# Module.net
KiCad netlist of a schematic drawn in Altium Designer
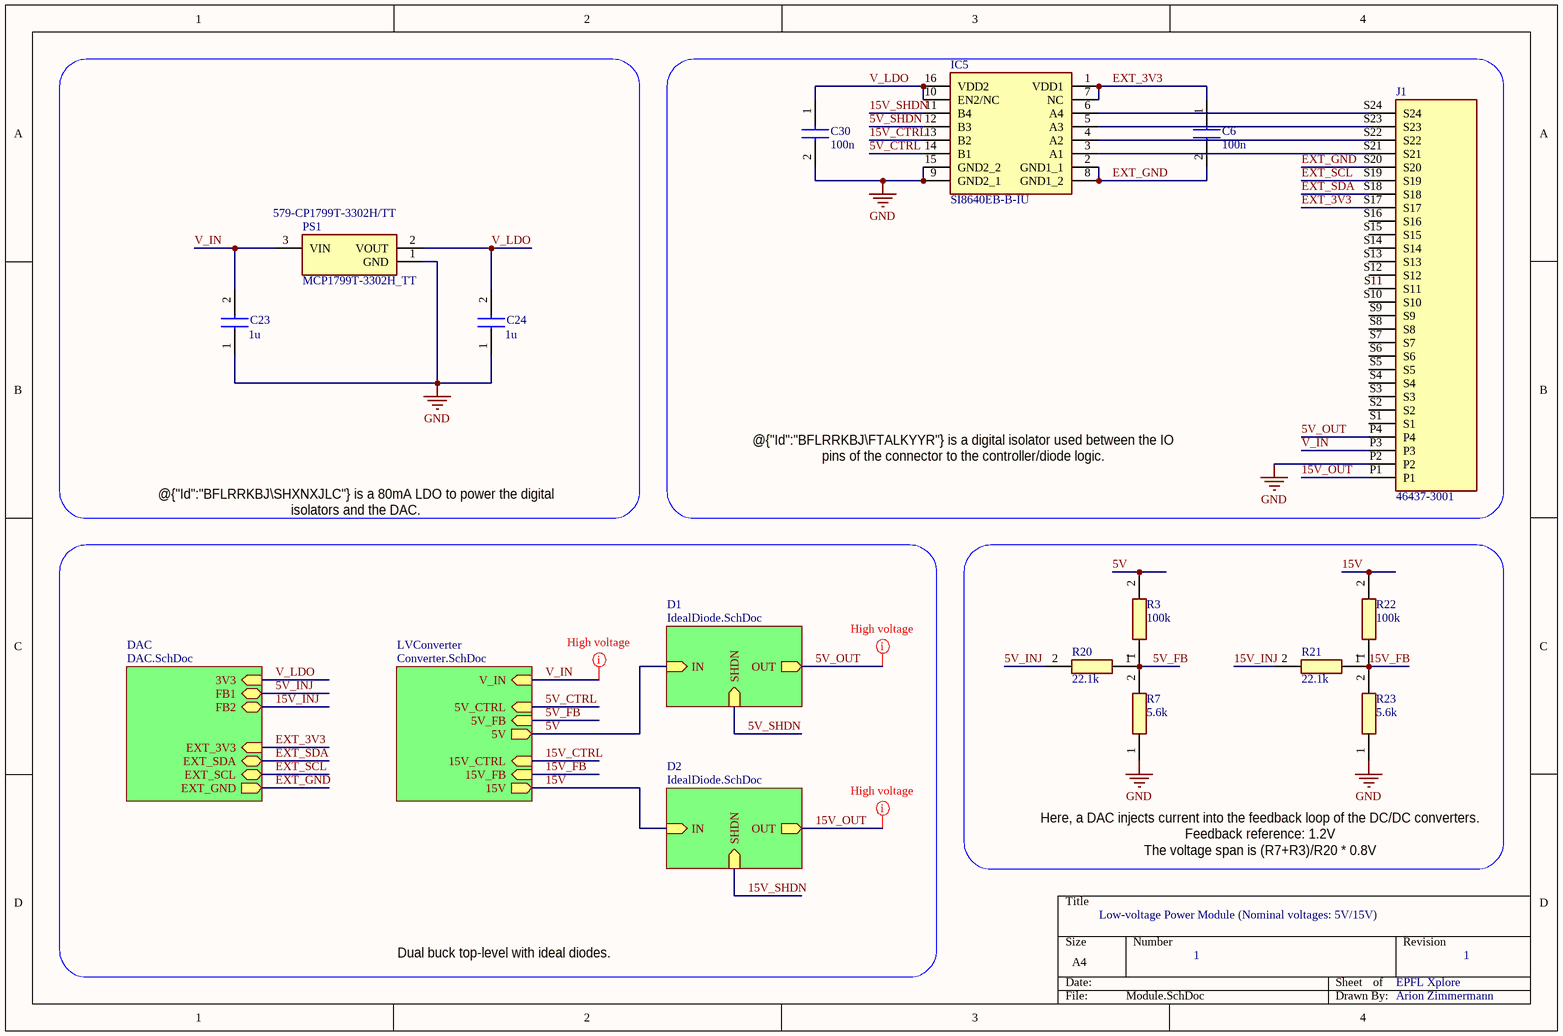
[diagram p0: Module.SchDoc]

(export (version "E")
  (design (tool "Eeschema 10.0.6"))
  (components
    (comp (ref "C6")
      (value "100n")
      (footprint "SamacSys:CAPC1608X95N")
      (description "Capacitor")
      (fields
        (field (name "MANUFACTURER_PART_NUMBER") "C0603C104K5RACTU")
        (field (name "MOUSER PART NUMBER") "80-C0603C104K5R")
      )
      (libsource (lib "*") (part "C0603C104K5RACTU"))
    )
    (comp (ref "C23")
      (value "1u")
      (footprint "SamacSys:CAPC3216X110N")
      (description "Capacitor")
      (fields
        (field (name "MANUFACTURER_PART_NUMBER") "C1206C105K5RAC")
        (field (name "MOUSER PART NUMBER") "80-C1206C105K5RAC")
      )
      (libsource (lib "*") (part "C1206C105K5RAC"))
    )
    (comp (ref "C24")
      (value "1u")
      (footprint "SamacSys:CAPC3216X110N")
      (description "Capacitor")
      (fields
        (field (name "MANUFACTURER_PART_NUMBER") "C1206C105K5RAC")
        (field (name "MOUSER PART NUMBER") "80-C1206C105K5RAC")
      )
      (libsource (lib "*") (part "C1206C105K5RAC"))
    )
    (comp (ref "C30")
      (value "100n")
      (footprint "SamacSys:CAPC1608X95N")
      (description "Capacitor")
      (fields
        (field (name "MANUFACTURER_PART_NUMBER") "C0603C104K5RACTU")
        (field (name "MOUSER PART NUMBER") "80-C0603C104K5R")
      )
      (libsource (lib "*") (part "C0603C104K5RACTU"))
    )
    (comp (ref "IC5")
      (value "SI8640EB-B-IU")
      (footprint "SamacSys:SOP64P600X175-16N")
      (description "Integrated Circuit")
      (fields (field (name "MOUSER PART NUMBER") "634-SI8640EB-B-IU"))
      (libsource (lib "*") (part "SI8640EB-B-IU"))
    )
    (comp (ref "J1")
      (value "46437-3001")
      (footprint "464373001")
      (description "Connector")
      (fields (field (name "MOUSER PART NUMBER") "538-46437-3001"))
      (libsource (lib "SamacSys") (part "46437-3001"))
    )
    (comp (ref "PS1")
      (value "MCP1799T-3302H_TT")
      (footprint "SamacSys:SOT95P237X112-3N")
      (description "Power Supply")
      (fields
        (field (name "MANUFACTURER_PART_NUMBER") "MCP1799T-3302H/TT")
        (field (name "MOUSER PART NUMBER") "579-CP1799T-3302H/TT")
        (field (name "SUPPLIER PART NUMBER 1") "579-CP1799T-3302H/TT")
      )
      (libsource (lib "*") (part "MCP1799T-3302H_TT"))
    )
    (comp (ref "R3")
      (value "100k")
      (footprint "SamacSys:RESC1608X55N")
      (description "Resistor")
      (fields
        (field (name "MANUFACTURER_PART_NUMBER") "CRCW0603100KFKEAC")
        (field (name "MOUSER PART NUMBER") "71-CRCW0603100KFKEAC")
      )
      (libsource (lib "*") (part "CRCW0603100KFKEAC"))
    )
    (comp (ref "R7")
      (value "5.6k")
      (footprint "SamacSys:RESC1608X50N")
      (description "Resistor")
      (fields
        (field (name "MANUFACTURER_PART_NUMBER") "CRCW06035K62FKEB")
        (field (name "MOUSER PART NUMBER") "71-CRCW06035K62FKEB")
      )
      (libsource (lib "*") (part "CRCW06035K62FKEB"))
    )
    (comp (ref "R20")
      (value "22.1k")
      (footprint "SamacSys:RESC1608X50N")
      (description "Resistor")
      (fields
        (field (name "MANUFACTURER_PART_NUMBER") "CRCW06037K50FKEB")
        (field (name "MOUSER PART NUMBER") "71-CRCW06037K50FKEB")
      )
      (libsource (lib "*") (part "CRCW06037K50FKEB"))
    )
    (comp (ref "R21")
      (value "22.1k")
      (footprint "SamacSys:RESC1608X50N")
      (description "Resistor")
      (fields
        (field (name "MANUFACTURER_PART_NUMBER") "CRCW06037K50FKEB")
        (field (name "MOUSER PART NUMBER") "71-CRCW06037K50FKEB")
      )
      (libsource (lib "*") (part "CRCW06037K50FKEB"))
    )
    (comp (ref "R22")
      (value "100k")
      (footprint "SamacSys:RESC1608X55N")
      (description "Resistor")
      (fields
        (field (name "MANUFACTURER_PART_NUMBER") "CRCW0603100KFKEAC")
        (field (name "MOUSER PART NUMBER") "71-CRCW0603100KFKEAC")
      )
      (libsource (lib "*") (part "CRCW0603100KFKEAC"))
    )
    (comp (ref "R23")
      (value "5.6k")
      (footprint "SamacSys:RESC1608X50N")
      (description "Resistor")
      (fields
        (field (name "MANUFACTURER_PART_NUMBER") "CRCW06035K62FKEB")
        (field (name "MOUSER PART NUMBER") "71-CRCW06035K62FKEB")
      )
      (libsource (lib "*") (part "CRCW06035K62FKEB"))
    )
  )
  (nets
    (net (code "1") (name "/5V") (class "Default")
      (node (ref "R3") (pin "2") (pinfunction "2_2") (pintype "passive"))
    )
    (net (code "2") (name "/5V_CTRL") (class "Default")
      (node (ref "IC5") (pin "14") (pinfunction "B1_14") (pintype "passive"))
    )
    (net (code "3") (name "/5V_FB") (class "Default")
      (node (ref "R20") (pin "1") (pinfunction "1_1") (pintype "passive"))
      (node (ref "R3") (pin "1") (pinfunction "1_1") (pintype "passive"))
      (node (ref "R7") (pin "2") (pinfunction "2_2") (pintype "passive"))
    )
    (net (code "4") (name "/5V_INJ") (class "Default")
      (node (ref "R20") (pin "2") (pinfunction "2_2") (pintype "passive"))
    )
    (net (code "5") (name "/5V_OUT") (class "Default")
      (node (ref "J1") (pin "P4") (pinfunction "P4_P4") (pintype "passive"))
    )
    (net (code "6") (name "/5V_SHDN") (class "Default")
      (node (ref "IC5") (pin "12") (pinfunction "B3_12") (pintype "passive"))
    )
    (net (code "7") (name "/15V") (class "Default")
      (node (ref "R22") (pin "2") (pinfunction "2_2") (pintype "passive"))
    )
    (net (code "8") (name "/15V_CTRL") (class "Default")
      (node (ref "IC5") (pin "13") (pinfunction "B2_13") (pintype "passive"))
    )
    (net (code "9") (name "/15V_FB") (class "Default")
      (node (ref "R21") (pin "1") (pinfunction "1_1") (pintype "passive"))
      (node (ref "R22") (pin "1") (pinfunction "1_1") (pintype "passive"))
      (node (ref "R23") (pin "2") (pinfunction "2_2") (pintype "passive"))
    )
    (net (code "10") (name "/15V_INJ") (class "Default")
      (node (ref "R21") (pin "2") (pinfunction "2_2") (pintype "passive"))
    )
    (net (code "11") (name "/15V_OUT") (class "Default")
      (node (ref "J1") (pin "P1") (pinfunction "P1_P1") (pintype "passive"))
    )
    (net (code "12") (name "/15V_SHDN") (class "Default")
      (node (ref "IC5") (pin "11") (pinfunction "B4_11") (pintype "passive"))
    )
    (net (code "13") (name "/EXT_3V3") (class "Default")
      (node (ref "C6") (pin "1") (pinfunction "1_1") (pintype "passive"))
      (node (ref "IC5") (pin "1") (pinfunction "VDD1_1") (pintype "passive"))
      (node (ref "IC5") (pin "7") (pinfunction "NC_7") (pintype "passive"))
      (node (ref "J1") (pin "S17") (pinfunction "S17_S17") (pintype "passive"))
    )
    (net (code "14") (name "/EXT_GND") (class "Default")
      (node (ref "C6") (pin "2") (pinfunction "2_2") (pintype "passive"))
      (node (ref "IC5") (pin "2") (pinfunction "GND1_1_2") (pintype "passive"))
      (node (ref "IC5") (pin "8") (pinfunction "GND1_2_8") (pintype "passive"))
      (node (ref "J1") (pin "S20") (pinfunction "S20_S20") (pintype "passive"))
    )
    (net (code "15") (name "/EXT_SCL") (class "Default")
      (node (ref "J1") (pin "S19") (pinfunction "S19_S19") (pintype "passive"))
    )
    (net (code "16") (name "/EXT_SDA") (class "Default")
      (node (ref "J1") (pin "S18") (pinfunction "S18_S18") (pintype "passive"))
    )
    (net (code "17") (name "/V_IN") (class "Default")
      (node (ref "C23") (pin "2") (pinfunction "2_2") (pintype "passive"))
      (node (ref "J1") (pin "P3") (pinfunction "P3_P3") (pintype "passive"))
      (node (ref "PS1") (pin "3") (pinfunction "VIN_3") (pintype "passive"))
    )
    (net (code "18") (name "/V_LDO") (class "Default")
      (node (ref "C24") (pin "2") (pinfunction "2_2") (pintype "passive"))
      (node (ref "C30") (pin "1") (pinfunction "1_1") (pintype "passive"))
      (node (ref "IC5") (pin "10") (pinfunction "EN2/NC_10") (pintype "passive"))
      (node (ref "IC5") (pin "16") (pinfunction "VDD2_16") (pintype "passive"))
      (node (ref "PS1") (pin "2") (pinfunction "VOUT_2") (pintype "passive"))
    )
    (net (code "19") (name "GND") (class "Default")
      (node (ref "C23") (pin "1") (pinfunction "1_1") (pintype "passive"))
      (node (ref "C24") (pin "1") (pinfunction "1_1") (pintype "passive"))
      (node (ref "C30") (pin "2") (pinfunction "2_2") (pintype "passive"))
      (node (ref "IC5") (pin "15") (pinfunction "GND2_2_15") (pintype "passive"))
      (node (ref "IC5") (pin "9") (pinfunction "GND2_1_9") (pintype "passive"))
      (node (ref "J1") (pin "P2") (pinfunction "P2_P2") (pintype "passive"))
      (node (ref "PS1") (pin "1") (pinfunction "GND_1") (pintype "passive"))
      (node (ref "R23") (pin "1") (pinfunction "1_1") (pintype "passive"))
      (node (ref "R7") (pin "1") (pinfunction "1_1") (pintype "passive"))
    )
    (net (code "20") (name "Net-(IC5-A1)") (class "Default")
      (node (ref "IC5") (pin "3") (pinfunction "A1_3") (pintype "passive"))
      (node (ref "J1") (pin "S21") (pinfunction "S21_S21") (pintype "passive"))
    )
    (net (code "21") (name "Net-(IC5-A2)") (class "Default")
      (node (ref "IC5") (pin "4") (pinfunction "A2_4") (pintype "passive"))
      (node (ref "J1") (pin "S22") (pinfunction "S22_S22") (pintype "passive"))
    )
    (net (code "22") (name "Net-(IC5-A3)") (class "Default")
      (node (ref "IC5") (pin "5") (pinfunction "A3_5") (pintype "passive"))
      (node (ref "J1") (pin "S23") (pinfunction "S23_S23") (pintype "passive"))
    )
    (net (code "23") (name "Net-(IC5-A4)") (class "Default")
      (node (ref "IC5") (pin "6") (pinfunction "A4_6") (pintype "passive"))
      (node (ref "J1") (pin "S24") (pinfunction "S24_S24") (pintype "passive"))
    )
    (net (code "24") (name "unconnected-(J1-PadS1)") (class "Default")
      (node (ref "J1") (pin "S1") (pinfunction "S1_S1") (pintype "passive"))
    )
    (net (code "25") (name "unconnected-(J1-PadS2)") (class "Default")
      (node (ref "J1") (pin "S2") (pinfunction "S2_S2") (pintype "passive"))
    )
    (net (code "26") (name "unconnected-(J1-PadS3)") (class "Default")
      (node (ref "J1") (pin "S3") (pinfunction "S3_S3") (pintype "passive"))
    )
    (net (code "27") (name "unconnected-(J1-PadS4)") (class "Default")
      (node (ref "J1") (pin "S4") (pinfunction "S4_S4") (pintype "passive"))
    )
    (net (code "28") (name "unconnected-(J1-PadS5)") (class "Default")
      (node (ref "J1") (pin "S5") (pinfunction "S5_S5") (pintype "passive"))
    )
    (net (code "29") (name "unconnected-(J1-PadS6)") (class "Default")
      (node (ref "J1") (pin "S6") (pinfunction "S6_S6") (pintype "passive"))
    )
    (net (code "30") (name "unconnected-(J1-PadS7)") (class "Default")
      (node (ref "J1") (pin "S7") (pinfunction "S7_S7") (pintype "passive"))
    )
    (net (code "31") (name "unconnected-(J1-PadS8)") (class "Default")
      (node (ref "J1") (pin "S8") (pinfunction "S8_S8") (pintype "passive"))
    )
    (net (code "32") (name "unconnected-(J1-PadS9)") (class "Default")
      (node (ref "J1") (pin "S9") (pinfunction "S9_S9") (pintype "passive"))
    )
    (net (code "33") (name "unconnected-(J1-PadS10)") (class "Default")
      (node (ref "J1") (pin "S10") (pinfunction "S10_S10") (pintype "passive"))
    )
    (net (code "34") (name "unconnected-(J1-PadS11)") (class "Default")
      (node (ref "J1") (pin "S11") (pinfunction "S11_S11") (pintype "passive"))
    )
    (net (code "35") (name "unconnected-(J1-PadS12)") (class "Default")
      (node (ref "J1") (pin "S12") (pinfunction "S12_S12") (pintype "passive"))
    )
    (net (code "36") (name "unconnected-(J1-PadS13)") (class "Default")
      (node (ref "J1") (pin "S13") (pinfunction "S13_S13") (pintype "passive"))
    )
    (net (code "37") (name "unconnected-(J1-PadS14)") (class "Default")
      (node (ref "J1") (pin "S14") (pinfunction "S14_S14") (pintype "passive"))
    )
    (net (code "38") (name "unconnected-(J1-PadS15)") (class "Default")
      (node (ref "J1") (pin "S15") (pinfunction "S15_S15") (pintype "passive"))
    )
    (net (code "39") (name "unconnected-(J1-PadS16)") (class "Default")
      (node (ref "J1") (pin "S16") (pinfunction "S16_S16") (pintype "passive"))
    )
  )
)
